# auxboxshield1_55.net
KiCad netlist of a schematic drawn in EAGLE
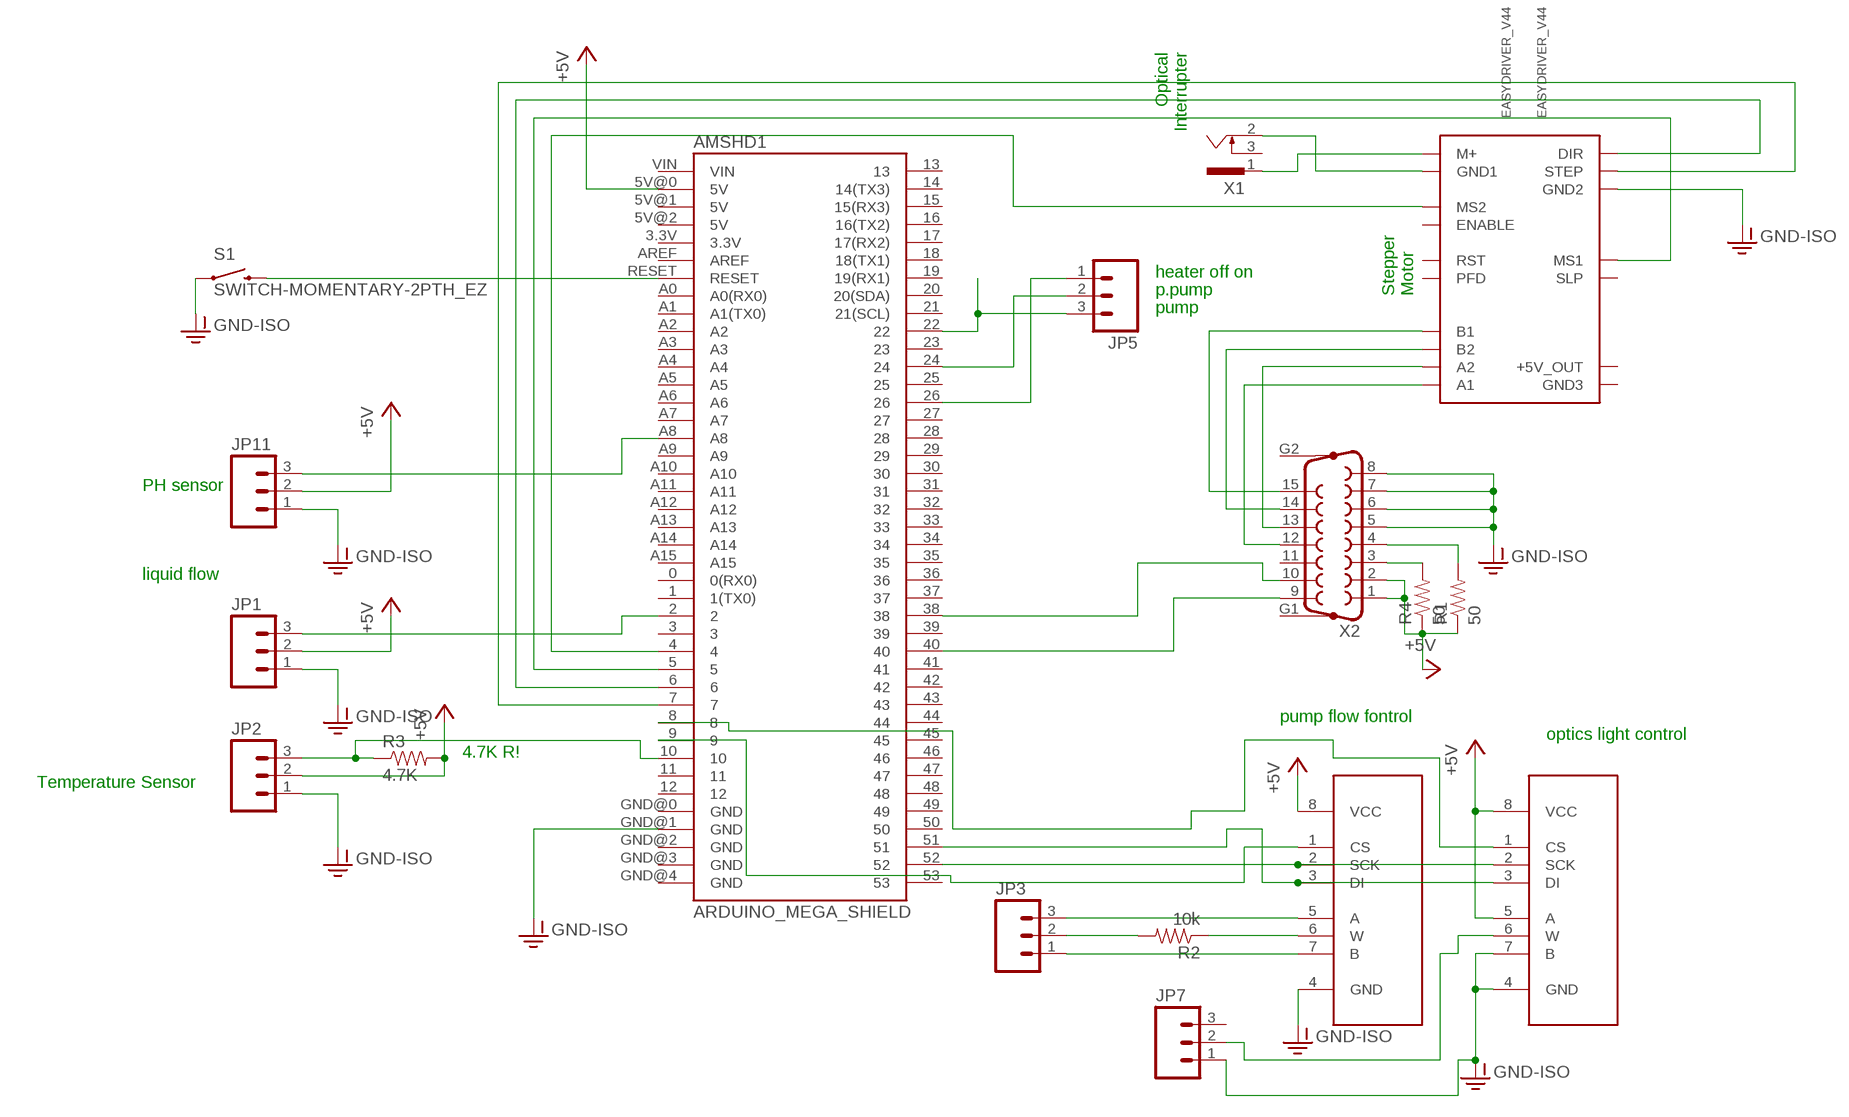
[diagram p0: schematic, sheet 1]

(export (version "E")
  (design (tool "Eeschema 10.0.6"))
  (components
    (comp (ref "AMSHD1")
      (value "ARDUINO_MEGA_SHIELD")
      (footprint "eagle-import:ARDUINO_MEGA_SHIELD")
      (libsource (lib "eagle-import") (part "ARDUINO_MEGA_SHIELD"))
    )
    (comp (ref "EASYDRIVER_V44")
      (value "EASYDRIVER_V44")
      (footprint "eagle-import:EASYDRIVER_V44")
      (libsource (lib "eagle-import") (part "EASYDRIVER_V44"))
    )
    (comp (ref "JP1")
      (value "M03POLAR")
      (footprint "eagle-import:MOLEX-1X3")
      (libsource (lib "eagle-import") (part "M03POLAR"))
    )
    (comp (ref "JP2")
      (value "M03POLAR")
      (footprint "eagle-import:MOLEX-1X3")
      (libsource (lib "eagle-import") (part "M03POLAR"))
    )
    (comp (ref "JP3")
      (value "M03POLAR")
      (footprint "eagle-import:MOLEX-1X3")
      (libsource (lib "eagle-import") (part "M03POLAR"))
    )
    (comp (ref "JP5")
      (value "M03POLAR")
      (footprint "eagle-import:MOLEX-1X3")
      (libsource (lib "eagle-import") (part "M03POLAR"))
    )
    (comp (ref "JP7")
      (value "M03POLAR")
      (footprint "eagle-import:MOLEX-1X3")
      (libsource (lib "eagle-import") (part "M03POLAR"))
    )
    (comp (ref "JP11")
      (value "M03POLAR")
      (footprint "eagle-import:MOLEX-1X3")
      (libsource (lib "eagle-import") (part "M03POLAR"))
    )
    (comp (ref "R1")
      (value "50")
      (footprint "eagle-import:AXIAL-0.3")
      (libsource (lib "eagle-import") (part "10OHM-1/4W-5%(PTH)"))
    )
    (comp (ref "R2")
      (value "10k")
      (footprint "eagle-import:AXIAL-0.3")
      (libsource (lib "eagle-import") (part "10KOHM-1/4W-1%(PTH)HORIZ"))
    )
    (comp (ref "R3")
      (value "4.7K")
      (footprint "eagle-import:AXIAL-0.3")
      (libsource (lib "eagle-import") (part "10OHM-1/4W-5%(PTH)"))
    )
    (comp (ref "R4")
      (value "50")
      (footprint "eagle-import:AXIAL-0.3")
      (libsource (lib "eagle-import") (part "10OHM-1/4W-5%(PTH)"))
    )
    (comp (ref "S1")
      (value "SWITCH-MOMENTARY-2PTH_EZ")
      (footprint "eagle-import:TACTILE-PTH-EZ")
      (libsource (lib "eagle-import") (part "SWITCH-MOMENTARY-2PTH_EZ"))
    )
    (comp (ref "U1")
      (value "MCP41XXXDIL")
      (footprint "eagle-import:DIL-08")
      (libsource (lib "eagle-import") (part "MCP41XXXDIL"))
    )
    (comp (ref "U2")
      (value "MCP41XXXDIL")
      (footprint "eagle-import:DIL-08")
      (libsource (lib "eagle-import") (part "MCP41XXXDIL"))
    )
    (comp (ref "X1")
      (value "SCD-014A")
      (footprint "eagle-import:SCD-014-A")
      (libsource (lib "eagle-import") (part "SCD-014A"))
    )
    (comp (ref "X2")
      (value "F15VP")
      (footprint "eagle-import:F15VP")
      (libsource (lib "eagle-import") (part "F15VP"))
    )
  )
  (nets
    (net (code "1") (name "+5V") (class "Default")
      (node (ref "AMSHD1") (pin "5V@0") (pinfunction "5V_5V@0") (pintype "bidirectional"))
      (node (ref "JP1") (pin "2") (pinfunction "2_2") (pintype "passive"))
      (node (ref "JP11") (pin "2") (pinfunction "2_2") (pintype "passive"))
      (node (ref "JP2") (pin "2") (pinfunction "2_2") (pintype "passive"))
      (node (ref "R1") (pin "P$1") (pinfunction "1_P$1") (pintype "passive"))
      (node (ref "R3") (pin "P$2") (pinfunction "2_P$2") (pintype "passive"))
      (node (ref "R4") (pin "P$1") (pinfunction "1_P$1") (pintype "passive"))
      (node (ref "U1") (pin "5") (pinfunction "A_5") (pintype "bidirectional"))
      (node (ref "U1") (pin "8") (pinfunction "VCC_8") (pintype "bidirectional"))
      (node (ref "U2") (pin "8") (pinfunction "VCC_8") (pintype "bidirectional"))
      (node (ref "X2") (pin "1") (pinfunction "1_1") (pintype "passive"))
      (node (ref "X2") (pin "2") (pinfunction "2_2") (pintype "passive"))
    )
    (net (code "2") (name "GND-ISO") (class "Default")
      (node (ref "AMSHD1") (pin "GND@1") (pinfunction "GND_GND@1") (pintype "bidirectional"))
      (node (ref "EASYDRIVER_V44") (pin "GND2") (pinfunction "GND2_GND2") (pintype "bidirectional"))
      (node (ref "JP1") (pin "1") (pinfunction "1_1") (pintype "passive"))
      (node (ref "JP11") (pin "1") (pinfunction "1_1") (pintype "passive"))
      (node (ref "JP2") (pin "1") (pinfunction "1_1") (pintype "passive"))
      (node (ref "JP7") (pin "1") (pinfunction "1_1") (pintype "passive"))
      (node (ref "S1") (pin "1") (pinfunction "1_1") (pintype "passive"))
      (node (ref "U1") (pin "4") (pinfunction "GND_4") (pintype "bidirectional"))
      (node (ref "U1") (pin "7") (pinfunction "B_7") (pintype "bidirectional"))
      (node (ref "U2") (pin "4") (pinfunction "GND_4") (pintype "bidirectional"))
      (node (ref "X2") (pin "5") (pinfunction "5_5") (pintype "passive"))
      (node (ref "X2") (pin "6") (pinfunction "6_6") (pintype "passive"))
      (node (ref "X2") (pin "7") (pinfunction "7_7") (pintype "passive"))
      (node (ref "X2") (pin "8") (pinfunction "8_8") (pintype "passive"))
    )
    (net (code "3") (name "Net-(AMSHD1-Pad2)") (class "Default")
      (node (ref "AMSHD1") (pin "2") (pinfunction "2_2") (pintype "bidirectional"))
      (node (ref "JP1") (pin "3") (pinfunction "3_3") (pintype "passive"))
    )
    (net (code "4") (name "Net-(AMSHD1-Pad4)") (class "Default")
      (node (ref "AMSHD1") (pin "4") (pinfunction "4_4") (pintype "bidirectional"))
      (node (ref "EASYDRIVER_V44") (pin "MS2") (pinfunction "MS2_MS2") (pintype "bidirectional"))
    )
    (net (code "5") (name "Net-(AMSHD1-Pad5)") (class "Default")
      (node (ref "AMSHD1") (pin "5") (pinfunction "5_5") (pintype "bidirectional"))
      (node (ref "EASYDRIVER_V44") (pin "MS1") (pinfunction "MS1_MS1") (pintype "bidirectional"))
    )
    (net (code "6") (name "Net-(AMSHD1-Pad6)") (class "Default")
      (node (ref "AMSHD1") (pin "6") (pinfunction "6_6") (pintype "bidirectional"))
      (node (ref "EASYDRIVER_V44") (pin "DIR") (pinfunction "DIR_DIR") (pintype "bidirectional"))
    )
    (net (code "7") (name "Net-(AMSHD1-Pad7)") (class "Default")
      (node (ref "AMSHD1") (pin "7") (pinfunction "7_7") (pintype "bidirectional"))
      (node (ref "EASYDRIVER_V44") (pin "STEP") (pinfunction "STEP_STEP") (pintype "bidirectional"))
    )
    (net (code "8") (name "Net-(AMSHD1-Pad22)") (class "Default")
      (node (ref "AMSHD1") (pin "22") (pinfunction "22_22") (pintype "bidirectional"))
      (node (ref "JP5") (pin "3") (pinfunction "3_3") (pintype "passive"))
    )
    (net (code "9") (name "Net-(AMSHD1-Pad24)") (class "Default")
      (node (ref "AMSHD1") (pin "24") (pinfunction "24_24") (pintype "bidirectional"))
      (node (ref "JP5") (pin "2") (pinfunction "2_2") (pintype "passive"))
    )
    (net (code "10") (name "Net-(AMSHD1-Pad26)") (class "Default")
      (node (ref "AMSHD1") (pin "26") (pinfunction "26_26") (pintype "bidirectional"))
      (node (ref "JP5") (pin "1") (pinfunction "1_1") (pintype "passive"))
    )
    (net (code "11") (name "Net-(AMSHD1-Pad38)") (class "Default")
      (node (ref "AMSHD1") (pin "38") (pinfunction "38_38") (pintype "bidirectional"))
      (node (ref "X2") (pin "10") (pinfunction "10_10") (pintype "passive"))
    )
    (net (code "12") (name "Net-(AMSHD1-Pad40)") (class "Default")
      (node (ref "AMSHD1") (pin "40") (pinfunction "40_40") (pintype "bidirectional"))
      (node (ref "X2") (pin "9") (pinfunction "9_9") (pintype "passive"))
    )
    (net (code "13") (name "Net-(AMSHD1-PadA8)") (class "Default")
      (node (ref "AMSHD1") (pin "A8") (pinfunction "A8_A8") (pintype "bidirectional"))
      (node (ref "JP11") (pin "3") (pinfunction "3_3") (pintype "passive"))
    )
    (net (code "14") (name "Net-(EASYDRIVER_V44-PadA1)") (class "Default")
      (node (ref "EASYDRIVER_V44") (pin "A1") (pinfunction "A1_A1") (pintype "bidirectional"))
      (node (ref "X2") (pin "12") (pinfunction "12_12") (pintype "passive"))
    )
    (net (code "15") (name "Net-(EASYDRIVER_V44-PadA2)") (class "Default")
      (node (ref "EASYDRIVER_V44") (pin "A2") (pinfunction "A2_A2") (pintype "bidirectional"))
      (node (ref "X2") (pin "13") (pinfunction "13_13") (pintype "passive"))
    )
    (net (code "16") (name "Net-(EASYDRIVER_V44-PadB1)") (class "Default")
      (node (ref "EASYDRIVER_V44") (pin "B1") (pinfunction "B1_B1") (pintype "bidirectional"))
      (node (ref "X2") (pin "15") (pinfunction "15_15") (pintype "passive"))
    )
    (net (code "17") (name "Net-(EASYDRIVER_V44-PadB2)") (class "Default")
      (node (ref "EASYDRIVER_V44") (pin "B2") (pinfunction "B2_B2") (pintype "bidirectional"))
      (node (ref "X2") (pin "14") (pinfunction "14_14") (pintype "passive"))
    )
    (net (code "18") (name "Net-(EASYDRIVER_V44-PadGND1)") (class "Default")
      (node (ref "EASYDRIVER_V44") (pin "GND1") (pinfunction "GND1_GND1") (pintype "bidirectional"))
      (node (ref "X1") (pin "2") (pinfunction "2_2") (pintype "passive"))
    )
    (net (code "19") (name "Net-(EASYDRIVER_V44-PadM+)") (class "Default")
      (node (ref "EASYDRIVER_V44") (pin "M+") (pinfunction "M+_M+") (pintype "bidirectional"))
      (node (ref "X1") (pin "1") (pinfunction "1_1") (pintype "passive"))
    )
    (net (code "20") (name "Net-(R1-2)") (class "Default")
      (node (ref "R1") (pin "P$2") (pinfunction "2_P$2") (pintype "passive"))
      (node (ref "X2") (pin "4") (pinfunction "4_4") (pintype "passive"))
    )
    (net (code "21") (name "Net-(R2-1)") (class "Default")
      (node (ref "R2") (pin "P$1") (pinfunction "1_P$1") (pintype "passive"))
      (node (ref "U2") (pin "6") (pinfunction "W_6") (pintype "bidirectional"))
    )
    (net (code "22") (name "Net-(R2-2)") (class "Default")
      (node (ref "JP3") (pin "2") (pinfunction "2_2") (pintype "passive"))
      (node (ref "R2") (pin "P$2") (pinfunction "2_P$2") (pintype "passive"))
    )
    (net (code "23") (name "Net-(R3-1)") (class "Default")
      (node (ref "AMSHD1") (pin "10") (pinfunction "10_10") (pintype "bidirectional"))
      (node (ref "JP2") (pin "3") (pinfunction "3_3") (pintype "passive"))
      (node (ref "R3") (pin "P$1") (pinfunction "1_P$1") (pintype "passive"))
    )
    (net (code "24") (name "Net-(R4-2)") (class "Default")
      (node (ref "R4") (pin "P$2") (pinfunction "2_P$2") (pintype "passive"))
      (node (ref "X2") (pin "3") (pinfunction "3_3") (pintype "passive"))
    )
    (net (code "25") (name "Net-(S1-2)") (class "Default")
      (node (ref "AMSHD1") (pin "RESET") (pinfunction "RESET_RESET") (pintype "bidirectional"))
      (node (ref "S1") (pin "3") (pinfunction "2_3") (pintype "passive"))
    )
    (net (code "26") (name "Net-(U1-CS)") (class "Default")
      (node (ref "AMSHD1") (pin "8") (pinfunction "8_8") (pintype "bidirectional"))
      (node (ref "U1") (pin "1") (pinfunction "CS_1") (pintype "bidirectional"))
    )
    (net (code "27") (name "Net-(U1-DI)") (class "Default")
      (node (ref "AMSHD1") (pin "51") (pinfunction "51_51") (pintype "bidirectional"))
      (node (ref "U1") (pin "3") (pinfunction "DI_3") (pintype "bidirectional"))
      (node (ref "U2") (pin "3") (pinfunction "DI_3") (pintype "bidirectional"))
    )
    (net (code "28") (name "Net-(U1-SCK)") (class "Default")
      (node (ref "AMSHD1") (pin "52") (pinfunction "52_52") (pintype "bidirectional"))
      (node (ref "U1") (pin "2") (pinfunction "SCK_2") (pintype "bidirectional"))
      (node (ref "U2") (pin "2") (pinfunction "SCK_2") (pintype "bidirectional"))
    )
    (net (code "29") (name "Net-(U1-W)") (class "Default")
      (node (ref "JP7") (pin "2") (pinfunction "2_2") (pintype "passive"))
      (node (ref "U1") (pin "6") (pinfunction "W_6") (pintype "bidirectional"))
    )
    (net (code "30") (name "Net-(U2-A)") (class "Default")
      (node (ref "JP3") (pin "3") (pinfunction "3_3") (pintype "passive"))
      (node (ref "U2") (pin "5") (pinfunction "A_5") (pintype "bidirectional"))
    )
    (net (code "31") (name "Net-(U2-B)") (class "Default")
      (node (ref "JP3") (pin "1") (pinfunction "1_1") (pintype "passive"))
      (node (ref "U2") (pin "7") (pinfunction "B_7") (pintype "bidirectional"))
    )
    (net (code "32") (name "Net-(U2-CS)") (class "Default")
      (node (ref "AMSHD1") (pin "9") (pinfunction "9_9") (pintype "bidirectional"))
      (node (ref "U2") (pin "1") (pinfunction "CS_1") (pintype "bidirectional"))
    )
    (net (code "33") (name "unconnected-(AMSHD1-0(RX0)-Pad0)") (class "Default")
      (node (ref "AMSHD1") (pin "0") (pinfunction "0(RX0)_0") (pintype "bidirectional"))
    )
    (net (code "34") (name "unconnected-(AMSHD1-1(TX0)-Pad1)") (class "Default")
      (node (ref "AMSHD1") (pin "1") (pinfunction "1(TX0)_1") (pintype "bidirectional"))
    )
    (net (code "35") (name "unconnected-(AMSHD1-5V-Pad5V@1)") (class "Default")
      (node (ref "AMSHD1") (pin "5V@1") (pinfunction "5V_5V@1") (pintype "bidirectional"))
    )
    (net (code "36") (name "unconnected-(AMSHD1-5V-Pad5V@2)") (class "Default")
      (node (ref "AMSHD1") (pin "5V@2") (pinfunction "5V_5V@2") (pintype "bidirectional"))
    )
    (net (code "37") (name "unconnected-(AMSHD1-14(TX3)-Pad14)") (class "Default")
      (node (ref "AMSHD1") (pin "14") (pinfunction "14(TX3)_14") (pintype "bidirectional"))
    )
    (net (code "38") (name "unconnected-(AMSHD1-15(RX3)-Pad15)") (class "Default")
      (node (ref "AMSHD1") (pin "15") (pinfunction "15(RX3)_15") (pintype "bidirectional"))
    )
    (net (code "39") (name "unconnected-(AMSHD1-16(TX2)-Pad16)") (class "Default")
      (node (ref "AMSHD1") (pin "16") (pinfunction "16(TX2)_16") (pintype "bidirectional"))
    )
    (net (code "40") (name "unconnected-(AMSHD1-17(RX2)-Pad17)") (class "Default")
      (node (ref "AMSHD1") (pin "17") (pinfunction "17(RX2)_17") (pintype "bidirectional"))
    )
    (net (code "41") (name "unconnected-(AMSHD1-18(TX1)-Pad18)") (class "Default")
      (node (ref "AMSHD1") (pin "18") (pinfunction "18(TX1)_18") (pintype "bidirectional"))
    )
    (net (code "42") (name "unconnected-(AMSHD1-19(RX1)-Pad19)") (class "Default")
      (node (ref "AMSHD1") (pin "19") (pinfunction "19(RX1)_19") (pintype "bidirectional"))
    )
    (net (code "43") (name "unconnected-(AMSHD1-20(SDA)-Pad20)") (class "Default")
      (node (ref "AMSHD1") (pin "20") (pinfunction "20(SDA)_20") (pintype "bidirectional"))
    )
    (net (code "44") (name "unconnected-(AMSHD1-21(SCL)-Pad21)") (class "Default")
      (node (ref "AMSHD1") (pin "21") (pinfunction "21(SCL)_21") (pintype "bidirectional"))
    )
    (net (code "45") (name "unconnected-(AMSHD1-A0(RX0)-PadA0)") (class "Default")
      (node (ref "AMSHD1") (pin "A0") (pinfunction "A0(RX0)_A0") (pintype "bidirectional"))
    )
    (net (code "46") (name "unconnected-(AMSHD1-A1(TX0)-PadA1)") (class "Default")
      (node (ref "AMSHD1") (pin "A1") (pinfunction "A1(TX0)_A1") (pintype "bidirectional"))
    )
    (net (code "47") (name "unconnected-(AMSHD1-GND-PadGND@0)") (class "Default")
      (node (ref "AMSHD1") (pin "GND@0") (pinfunction "GND_GND@0") (pintype "bidirectional"))
    )
    (net (code "48") (name "unconnected-(AMSHD1-GND-PadGND@2)") (class "Default")
      (node (ref "AMSHD1") (pin "GND@2") (pinfunction "GND_GND@2") (pintype "bidirectional"))
    )
    (net (code "49") (name "unconnected-(AMSHD1-GND-PadGND@3)") (class "Default")
      (node (ref "AMSHD1") (pin "GND@3") (pinfunction "GND_GND@3") (pintype "bidirectional"))
    )
    (net (code "50") (name "unconnected-(AMSHD1-GND-PadGND@4)") (class "Default")
      (node (ref "AMSHD1") (pin "GND@4") (pinfunction "GND_GND@4") (pintype "bidirectional"))
    )
    (net (code "51") (name "unconnected-(AMSHD1-Pad3)") (class "Default")
      (node (ref "AMSHD1") (pin "3") (pinfunction "3_3") (pintype "bidirectional"))
    )
    (net (code "52") (name "unconnected-(AMSHD1-Pad3.3V)") (class "Default")
      (node (ref "AMSHD1") (pin "3.3V") (pinfunction "3.3V_3.3V") (pintype "bidirectional"))
    )
    (net (code "53") (name "unconnected-(AMSHD1-Pad11)") (class "Default")
      (node (ref "AMSHD1") (pin "11") (pinfunction "11_11") (pintype "bidirectional"))
    )
    (net (code "54") (name "unconnected-(AMSHD1-Pad12)") (class "Default")
      (node (ref "AMSHD1") (pin "12") (pinfunction "12_12") (pintype "bidirectional"))
    )
    (net (code "55") (name "unconnected-(AMSHD1-Pad13)") (class "Default")
      (node (ref "AMSHD1") (pin "13") (pinfunction "13_13") (pintype "bidirectional"))
    )
    (net (code "56") (name "unconnected-(AMSHD1-Pad23)") (class "Default")
      (node (ref "AMSHD1") (pin "23") (pinfunction "23_23") (pintype "bidirectional"))
    )
    (net (code "57") (name "unconnected-(AMSHD1-Pad25)") (class "Default")
      (node (ref "AMSHD1") (pin "25") (pinfunction "25_25") (pintype "bidirectional"))
    )
    (net (code "58") (name "unconnected-(AMSHD1-Pad27)") (class "Default")
      (node (ref "AMSHD1") (pin "27") (pinfunction "27_27") (pintype "bidirectional"))
    )
    (net (code "59") (name "unconnected-(AMSHD1-Pad28)") (class "Default")
      (node (ref "AMSHD1") (pin "28") (pinfunction "28_28") (pintype "bidirectional"))
    )
    (net (code "60") (name "unconnected-(AMSHD1-Pad29)") (class "Default")
      (node (ref "AMSHD1") (pin "29") (pinfunction "29_29") (pintype "bidirectional"))
    )
    (net (code "61") (name "unconnected-(AMSHD1-Pad30)") (class "Default")
      (node (ref "AMSHD1") (pin "30") (pinfunction "30_30") (pintype "bidirectional"))
    )
    (net (code "62") (name "unconnected-(AMSHD1-Pad31)") (class "Default")
      (node (ref "AMSHD1") (pin "31") (pinfunction "31_31") (pintype "bidirectional"))
    )
    (net (code "63") (name "unconnected-(AMSHD1-Pad32)") (class "Default")
      (node (ref "AMSHD1") (pin "32") (pinfunction "32_32") (pintype "bidirectional"))
    )
    (net (code "64") (name "unconnected-(AMSHD1-Pad33)") (class "Default")
      (node (ref "AMSHD1") (pin "33") (pinfunction "33_33") (pintype "bidirectional"))
    )
    (net (code "65") (name "unconnected-(AMSHD1-Pad34)") (class "Default")
      (node (ref "AMSHD1") (pin "34") (pinfunction "34_34") (pintype "bidirectional"))
    )
    (net (code "66") (name "unconnected-(AMSHD1-Pad35)") (class "Default")
      (node (ref "AMSHD1") (pin "35") (pinfunction "35_35") (pintype "bidirectional"))
    )
    (net (code "67") (name "unconnected-(AMSHD1-Pad36)") (class "Default")
      (node (ref "AMSHD1") (pin "36") (pinfunction "36_36") (pintype "bidirectional"))
    )
    (net (code "68") (name "unconnected-(AMSHD1-Pad37)") (class "Default")
      (node (ref "AMSHD1") (pin "37") (pinfunction "37_37") (pintype "bidirectional"))
    )
    (net (code "69") (name "unconnected-(AMSHD1-Pad39)") (class "Default")
      (node (ref "AMSHD1") (pin "39") (pinfunction "39_39") (pintype "bidirectional"))
    )
    (net (code "70") (name "unconnected-(AMSHD1-Pad41)") (class "Default")
      (node (ref "AMSHD1") (pin "41") (pinfunction "41_41") (pintype "bidirectional"))
    )
    (net (code "71") (name "unconnected-(AMSHD1-Pad42)") (class "Default")
      (node (ref "AMSHD1") (pin "42") (pinfunction "42_42") (pintype "bidirectional"))
    )
    (net (code "72") (name "unconnected-(AMSHD1-Pad43)") (class "Default")
      (node (ref "AMSHD1") (pin "43") (pinfunction "43_43") (pintype "bidirectional"))
    )
    (net (code "73") (name "unconnected-(AMSHD1-Pad44)") (class "Default")
      (node (ref "AMSHD1") (pin "44") (pinfunction "44_44") (pintype "bidirectional"))
    )
    (net (code "74") (name "unconnected-(AMSHD1-Pad45)") (class "Default")
      (node (ref "AMSHD1") (pin "45") (pinfunction "45_45") (pintype "bidirectional"))
    )
    (net (code "75") (name "unconnected-(AMSHD1-Pad46)") (class "Default")
      (node (ref "AMSHD1") (pin "46") (pinfunction "46_46") (pintype "bidirectional"))
    )
    (net (code "76") (name "unconnected-(AMSHD1-Pad47)") (class "Default")
      (node (ref "AMSHD1") (pin "47") (pinfunction "47_47") (pintype "bidirectional"))
    )
    (net (code "77") (name "unconnected-(AMSHD1-Pad48)") (class "Default")
      (node (ref "AMSHD1") (pin "48") (pinfunction "48_48") (pintype "bidirectional"))
    )
    (net (code "78") (name "unconnected-(AMSHD1-Pad49)") (class "Default")
      (node (ref "AMSHD1") (pin "49") (pinfunction "49_49") (pintype "bidirectional"))
    )
    (net (code "79") (name "unconnected-(AMSHD1-Pad50)") (class "Default")
      (node (ref "AMSHD1") (pin "50") (pinfunction "50_50") (pintype "bidirectional"))
    )
    (net (code "80") (name "unconnected-(AMSHD1-Pad53)") (class "Default")
      (node (ref "AMSHD1") (pin "53") (pinfunction "53_53") (pintype "bidirectional"))
    )
    (net (code "81") (name "unconnected-(AMSHD1-PadA2)") (class "Default")
      (node (ref "AMSHD1") (pin "A2") (pinfunction "A2_A2") (pintype "bidirectional"))
    )
    (net (code "82") (name "unconnected-(AMSHD1-PadA3)") (class "Default")
      (node (ref "AMSHD1") (pin "A3") (pinfunction "A3_A3") (pintype "bidirectional"))
    )
    (net (code "83") (name "unconnected-(AMSHD1-PadA4)") (class "Default")
      (node (ref "AMSHD1") (pin "A4") (pinfunction "A4_A4") (pintype "bidirectional"))
    )
    (net (code "84") (name "unconnected-(AMSHD1-PadA5)") (class "Default")
      (node (ref "AMSHD1") (pin "A5") (pinfunction "A5_A5") (pintype "bidirectional"))
    )
    (net (code "85") (name "unconnected-(AMSHD1-PadA6)") (class "Default")
      (node (ref "AMSHD1") (pin "A6") (pinfunction "A6_A6") (pintype "bidirectional"))
    )
    (net (code "86") (name "unconnected-(AMSHD1-PadA7)") (class "Default")
      (node (ref "AMSHD1") (pin "A7") (pinfunction "A7_A7") (pintype "bidirectional"))
    )
    (net (code "87") (name "unconnected-(AMSHD1-PadA9)") (class "Default")
      (node (ref "AMSHD1") (pin "A9") (pinfunction "A9_A9") (pintype "bidirectional"))
    )
    (net (code "88") (name "unconnected-(AMSHD1-PadA10)") (class "Default")
      (node (ref "AMSHD1") (pin "A10") (pinfunction "A10_A10") (pintype "bidirectional"))
    )
    (net (code "89") (name "unconnected-(AMSHD1-PadA11)") (class "Default")
      (node (ref "AMSHD1") (pin "A11") (pinfunction "A11_A11") (pintype "bidirectional"))
    )
    (net (code "90") (name "unconnected-(AMSHD1-PadA12)") (class "Default")
      (node (ref "AMSHD1") (pin "A12") (pinfunction "A12_A12") (pintype "bidirectional"))
    )
    (net (code "91") (name "unconnected-(AMSHD1-PadA13)") (class "Default")
      (node (ref "AMSHD1") (pin "A13") (pinfunction "A13_A13") (pintype "bidirectional"))
    )
    (net (code "92") (name "unconnected-(AMSHD1-PadA14)") (class "Default")
      (node (ref "AMSHD1") (pin "A14") (pinfunction "A14_A14") (pintype "bidirectional"))
    )
    (net (code "93") (name "unconnected-(AMSHD1-PadA15)") (class "Default")
      (node (ref "AMSHD1") (pin "A15") (pinfunction "A15_A15") (pintype "bidirectional"))
    )
    (net (code "94") (name "unconnected-(AMSHD1-PadAREF)") (class "Default")
      (node (ref "AMSHD1") (pin "AREF") (pinfunction "AREF_AREF") (pintype "bidirectional"))
    )
    (net (code "95") (name "unconnected-(AMSHD1-PadVIN)") (class "Default")
      (node (ref "AMSHD1") (pin "VIN") (pinfunction "VIN_VIN") (pintype "bidirectional"))
    )
    (net (code "96") (name "unconnected-(EASYDRIVER_V44-+5V_OUT-PadP$11)") (class "Default")
      (node (ref "EASYDRIVER_V44") (pin "P$11") (pinfunction "+5V_OUT_P$11") (pintype "bidirectional"))
    )
    (net (code "97") (name "unconnected-(EASYDRIVER_V44-PadENABLE)") (class "Default")
      (node (ref "EASYDRIVER_V44") (pin "ENABLE") (pinfunction "ENABLE_ENABLE") (pintype "bidirectional"))
    )
    (net (code "98") (name "unconnected-(EASYDRIVER_V44-PadGND3)") (class "Default")
      (node (ref "EASYDRIVER_V44") (pin "GND3") (pinfunction "GND3_GND3") (pintype "bidirectional"))
    )
    (net (code "99") (name "unconnected-(EASYDRIVER_V44-PadPFD)") (class "Default")
      (node (ref "EASYDRIVER_V44") (pin "PFD") (pinfunction "PFD_PFD") (pintype "bidirectional"))
    )
    (net (code "100") (name "unconnected-(EASYDRIVER_V44-PadRST)") (class "Default")
      (node (ref "EASYDRIVER_V44") (pin "RST") (pinfunction "RST_RST") (pintype "bidirectional"))
    )
    (net (code "101") (name "unconnected-(EASYDRIVER_V44-SLP-PadSLEEP)") (class "Default")
      (node (ref "EASYDRIVER_V44") (pin "SLEEP") (pinfunction "SLP_SLEEP") (pintype "bidirectional"))
    )
    (net (code "102") (name "unconnected-(JP7-Pad3)") (class "Default")
      (node (ref "JP7") (pin "3") (pinfunction "3_3") (pintype "passive"))
    )
    (net (code "103") (name "unconnected-(X1-Pad3)") (class "Default")
      (node (ref "X1") (pin "3") (pinfunction "3_3") (pintype "passive"))
    )
    (net (code "104") (name "unconnected-(X2-Pad11)") (class "Default")
      (node (ref "X2") (pin "11") (pinfunction "11_11") (pintype "passive"))
    )
    (net (code "105") (name "unconnected-(X2-PadG1)") (class "Default")
      (node (ref "X2") (pin "G1") (pinfunction "G1_G1") (pintype "passive"))
    )
    (net (code "106") (name "unconnected-(X2-PadG2)") (class "Default")
      (node (ref "X2") (pin "G2") (pinfunction "G2_G2") (pintype "passive"))
    )
  )
)
